# SmartSwitchBoard2x1.net
KiCad netlist of a schematic drawn in EAGLE
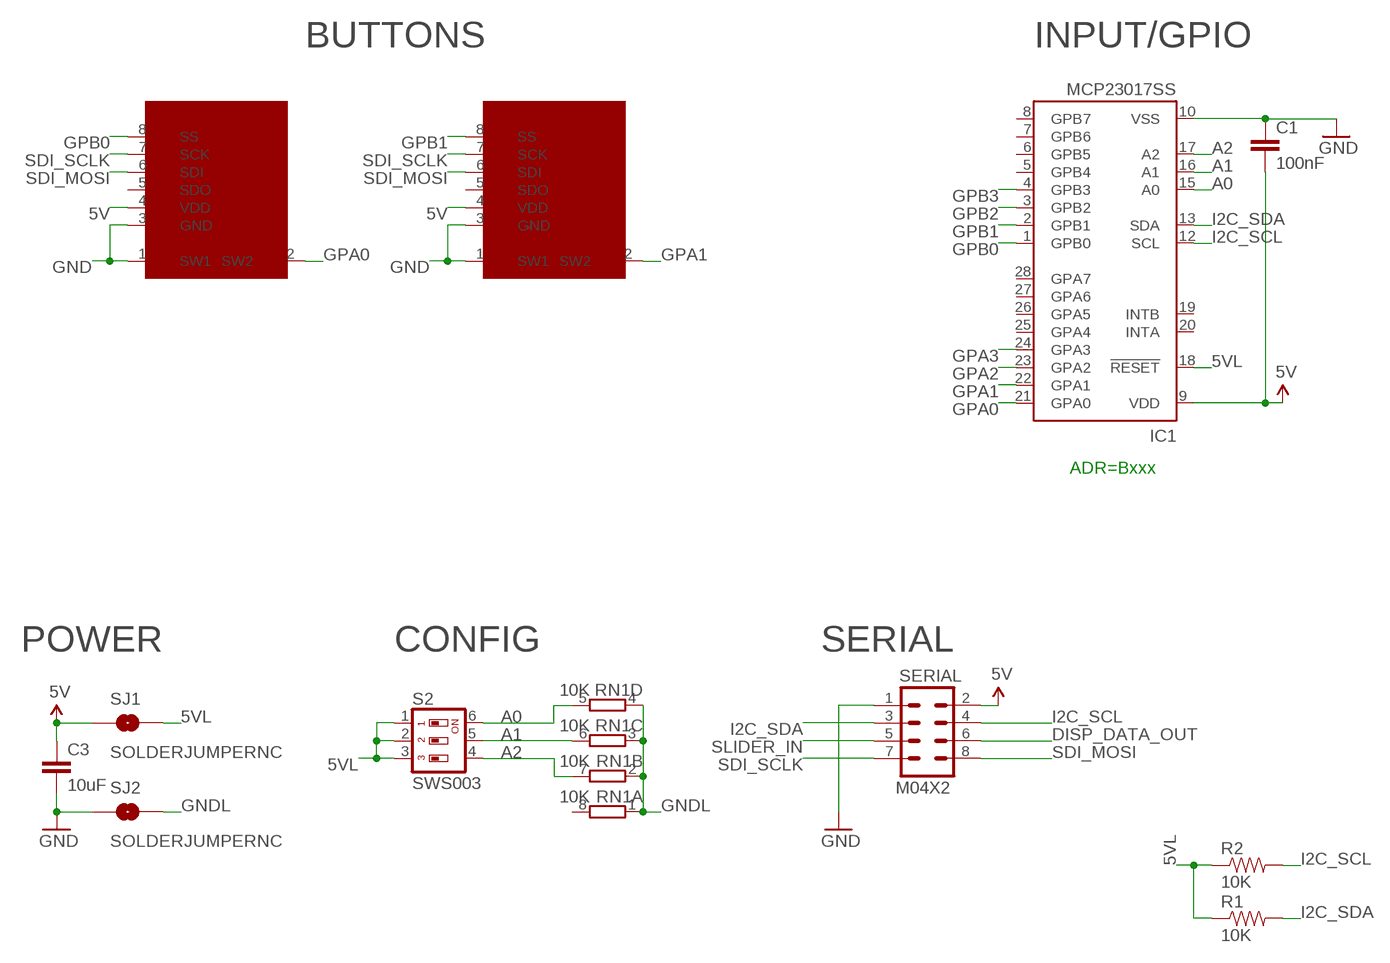
[diagram p0: schematic, sheet 1]

(export (version "E")
  (design (tool "Eeschema 10.0.6"))
  (components
    (comp (ref "C1")
      (value "100nF")
      (footprint "eagle-import:0603-CAP")
      (libsource (lib "eagle-import") (part "CAP0603-CAP"))
    )
    (comp (ref "C3")
      (value "10uF")
      (footprint "eagle-import:0805")
      (libsource (lib "eagle-import") (part "CAP0805"))
    )
    (comp (ref "IC1")
      (value "MCP23017SS")
      (footprint "eagle-import:SSOP28")
      (fields
        (field (name "MF") "MICROCHIP")
        (field (name "MPN") "MCP23017-E/SS")
        (field (name "MPN_1") "MCP23017-E/SS")
        (field (name "OC_FARNELL") "1467674")
        (field (name "OC_NEWARK") "31K2960")
      )
      (libsource (lib "eagle-import") (part "MCP23017SS"))
    )
    (comp (ref "R1")
      (value "10K")
      (footprint "eagle-import:0603-RES")
      (libsource (lib "eagle-import") (part "RESISTOR0603-RES"))
    )
    (comp (ref "R2")
      (value "10K")
      (footprint "eagle-import:0603-RES")
      (libsource (lib "eagle-import") (part "RESISTOR0603-RES"))
    )
    (comp (ref "RN1")
      (value "10K")
      (footprint "eagle-import:CAY16_HAND")
      (libsource (lib "eagle-import") (part "4R-NCAY16"))
    )
    (comp (ref "S2")
      (value "SWS003")
      (footprint "eagle-import:SMS-003")
      (libsource (lib "eagle-import") (part "SWS003"))
    )
    (comp (ref "SERIAL")
      (value "M04X2")
      (footprint "eagle-import:2X4")
      (libsource (lib "eagle-import") (part "M04X2"))
    )
    (comp (ref "SJ1")
      (value "SOLDERJUMPERNC")
      (footprint "eagle-import:SJ_2S")
      (libsource (lib "eagle-import") (part "SOLDERJUMPERNC"))
    )
    (comp (ref "SJ2")
      (value "SOLDERJUMPERNC")
      (footprint "eagle-import:SJ_2S")
      (libsource (lib "eagle-import") (part "SOLDERJUMPERNC"))
    )
    (comp (ref "U$2")
      (value "SMART_SWITCHSMART_SWITCH_8PIN")
      (footprint "eagle-import:SMART_SWITCH")
      (libsource (lib "eagle-import") (part "SMART_SWITCHSMART_SWITCH_8PIN"))
    )
    (comp (ref "U$3")
      (value "SMART_SWITCHSMART_SWITCH_8PIN")
      (footprint "eagle-import:SMART_SWITCH")
      (libsource (lib "eagle-import") (part "SMART_SWITCHSMART_SWITCH_8PIN"))
    )
  )
  (nets
    (net (code "1") (name "/5VL") (class "Default")
      (node (ref "IC1") (pin "18") (pinfunction "~{RESET}_18") (pintype "input"))
      (node (ref "R1") (pin "1") (pinfunction "1_1") (pintype "passive"))
      (node (ref "R2") (pin "1") (pinfunction "1_1") (pintype "passive"))
      (node (ref "S2") (pin "1") (pinfunction "1_1") (pintype "passive"))
      (node (ref "S2") (pin "2") (pinfunction "2_2") (pintype "passive"))
      (node (ref "S2") (pin "3") (pinfunction "3_3") (pintype "passive"))
      (node (ref "SJ1") (pin "2") (pinfunction "2_2") (pintype "passive"))
    )
    (net (code "2") (name "/A0") (class "Default")
      (node (ref "IC1") (pin "15") (pinfunction "A0_15") (pintype "input"))
      (node (ref "RN1") (pin "5") (pinfunction "2_5") (pintype "passive"))
      (node (ref "S2") (pin "6") (pinfunction "6_6") (pintype "passive"))
    )
    (net (code "3") (name "/A1") (class "Default")
      (node (ref "IC1") (pin "16") (pinfunction "A1_16") (pintype "input"))
      (node (ref "RN1") (pin "6") (pinfunction "2_6") (pintype "passive"))
      (node (ref "S2") (pin "5") (pinfunction "5_5") (pintype "passive"))
    )
    (net (code "4") (name "/A2") (class "Default")
      (node (ref "IC1") (pin "17") (pinfunction "A2_17") (pintype "input"))
      (node (ref "RN1") (pin "7") (pinfunction "2_7") (pintype "passive"))
      (node (ref "S2") (pin "4") (pinfunction "4_4") (pintype "passive"))
    )
    (net (code "5") (name "/DISP_DATA_OUT") (class "Default")
      (node (ref "SERIAL") (pin "6") (pinfunction "6_6") (pintype "passive"))
    )
    (net (code "6") (name "/GNDL") (class "Default")
      (node (ref "RN1") (pin "1") (pinfunction "1_1") (pintype "passive"))
      (node (ref "RN1") (pin "2") (pinfunction "1_2") (pintype "passive"))
      (node (ref "RN1") (pin "3") (pinfunction "1_3") (pintype "passive"))
      (node (ref "RN1") (pin "4") (pinfunction "1_4") (pintype "passive"))
      (node (ref "SJ2") (pin "2") (pinfunction "2_2") (pintype "passive"))
    )
    (net (code "7") (name "/GPA0") (class "Default")
      (node (ref "IC1") (pin "21") (pinfunction "GPA0_21") (pintype "bidirectional"))
      (node (ref "U$2") (pin "2") (pinfunction "SW2_2") (pintype "bidirectional"))
    )
    (net (code "8") (name "/GPA1") (class "Default")
      (node (ref "IC1") (pin "22") (pinfunction "GPA1_22") (pintype "bidirectional"))
      (node (ref "U$3") (pin "2") (pinfunction "SW2_2") (pintype "bidirectional"))
    )
    (net (code "9") (name "/GPA2") (class "Default")
      (node (ref "IC1") (pin "23") (pinfunction "GPA2_23") (pintype "bidirectional"))
    )
    (net (code "10") (name "/GPA3") (class "Default")
      (node (ref "IC1") (pin "24") (pinfunction "GPA3_24") (pintype "bidirectional"))
    )
    (net (code "11") (name "/GPB0") (class "Default")
      (node (ref "IC1") (pin "1") (pinfunction "GPB0_1") (pintype "bidirectional"))
      (node (ref "U$2") (pin "8") (pinfunction "SS_8") (pintype "bidirectional"))
    )
    (net (code "12") (name "/GPB1") (class "Default")
      (node (ref "IC1") (pin "2") (pinfunction "GPB1_2") (pintype "bidirectional"))
      (node (ref "U$3") (pin "8") (pinfunction "SS_8") (pintype "bidirectional"))
    )
    (net (code "13") (name "/GPB2") (class "Default")
      (node (ref "IC1") (pin "3") (pinfunction "GPB2_3") (pintype "bidirectional"))
    )
    (net (code "14") (name "/GPB3") (class "Default")
      (node (ref "IC1") (pin "4") (pinfunction "GPB3_4") (pintype "bidirectional"))
    )
    (net (code "15") (name "/I2C_SCL") (class "Default")
      (node (ref "IC1") (pin "12") (pinfunction "SCL_12") (pintype "input"))
      (node (ref "R2") (pin "2") (pinfunction "2_2") (pintype "passive"))
      (node (ref "SERIAL") (pin "4") (pinfunction "4_4") (pintype "passive"))
    )
    (net (code "16") (name "/I2C_SDA") (class "Default")
      (node (ref "IC1") (pin "13") (pinfunction "SDA_13") (pintype "bidirectional"))
      (node (ref "R1") (pin "2") (pinfunction "2_2") (pintype "passive"))
      (node (ref "SERIAL") (pin "3") (pinfunction "3_3") (pintype "passive"))
    )
    (net (code "17") (name "/SDI_MOSI") (class "Default")
      (node (ref "SERIAL") (pin "8") (pinfunction "8_8") (pintype "passive"))
      (node (ref "U$2") (pin "6") (pinfunction "SDI_6") (pintype "bidirectional"))
      (node (ref "U$3") (pin "6") (pinfunction "SDI_6") (pintype "bidirectional"))
    )
    (net (code "18") (name "/SDI_SCLK") (class "Default")
      (node (ref "SERIAL") (pin "7") (pinfunction "7_7") (pintype "passive"))
      (node (ref "U$2") (pin "7") (pinfunction "SCK_7") (pintype "bidirectional"))
      (node (ref "U$3") (pin "7") (pinfunction "SCK_7") (pintype "bidirectional"))
    )
    (net (code "19") (name "/SLIDER_IN") (class "Default")
      (node (ref "SERIAL") (pin "5") (pinfunction "5_5") (pintype "passive"))
    )
    (net (code "20") (name "5V") (class "Default")
      (node (ref "C1") (pin "2") (pinfunction "2_2") (pintype "passive"))
      (node (ref "C3") (pin "1") (pinfunction "1_1") (pintype "passive"))
      (node (ref "IC1") (pin "9") (pinfunction "VDD_9") (pintype "power_in"))
      (node (ref "SERIAL") (pin "2") (pinfunction "2_2") (pintype "passive"))
      (node (ref "SJ1") (pin "1") (pinfunction "1_1") (pintype "passive"))
      (node (ref "U$2") (pin "4") (pinfunction "VDD_4") (pintype "bidirectional"))
      (node (ref "U$3") (pin "4") (pinfunction "VDD_4") (pintype "bidirectional"))
    )
    (net (code "21") (name "GND") (class "Default")
      (node (ref "C1") (pin "1") (pinfunction "1_1") (pintype "passive"))
      (node (ref "C3") (pin "2") (pinfunction "2_2") (pintype "passive"))
      (node (ref "IC1") (pin "10") (pinfunction "VSS_10") (pintype "power_in"))
      (node (ref "SERIAL") (pin "1") (pinfunction "1_1") (pintype "passive"))
      (node (ref "SJ2") (pin "1") (pinfunction "1_1") (pintype "passive"))
      (node (ref "U$2") (pin "1") (pinfunction "SW1_1") (pintype "bidirectional"))
      (node (ref "U$2") (pin "3") (pinfunction "GND_3") (pintype "bidirectional"))
      (node (ref "U$3") (pin "1") (pinfunction "SW1_1") (pintype "bidirectional"))
      (node (ref "U$3") (pin "3") (pinfunction "GND_3") (pintype "bidirectional"))
    )
    (net (code "22") (name "unconnected-(IC1-GPA4-Pad25)") (class "Default")
      (node (ref "IC1") (pin "25") (pinfunction "GPA4_25") (pintype "bidirectional"))
    )
    (net (code "23") (name "unconnected-(IC1-GPA5-Pad26)") (class "Default")
      (node (ref "IC1") (pin "26") (pinfunction "GPA5_26") (pintype "bidirectional"))
    )
    (net (code "24") (name "unconnected-(IC1-GPA6-Pad27)") (class "Default")
      (node (ref "IC1") (pin "27") (pinfunction "GPA6_27") (pintype "bidirectional"))
    )
    (net (code "25") (name "unconnected-(IC1-GPA7-Pad28)") (class "Default")
      (node (ref "IC1") (pin "28") (pinfunction "GPA7_28") (pintype "bidirectional"))
    )
    (net (code "26") (name "unconnected-(IC1-GPB4-Pad5)") (class "Default")
      (node (ref "IC1") (pin "5") (pinfunction "GPB4_5") (pintype "bidirectional"))
    )
    (net (code "27") (name "unconnected-(IC1-GPB5-Pad6)") (class "Default")
      (node (ref "IC1") (pin "6") (pinfunction "GPB5_6") (pintype "bidirectional"))
    )
    (net (code "28") (name "unconnected-(IC1-GPB6-Pad7)") (class "Default")
      (node (ref "IC1") (pin "7") (pinfunction "GPB6_7") (pintype "bidirectional"))
    )
    (net (code "29") (name "unconnected-(IC1-GPB7-Pad8)") (class "Default")
      (node (ref "IC1") (pin "8") (pinfunction "GPB7_8") (pintype "bidirectional"))
    )
    (net (code "30") (name "unconnected-(IC1-INTA-Pad20)") (class "Default")
      (node (ref "IC1") (pin "20") (pinfunction "INTA_20") (pintype "output"))
    )
    (net (code "31") (name "unconnected-(IC1-INTB-Pad19)") (class "Default")
      (node (ref "IC1") (pin "19") (pinfunction "INTB_19") (pintype "output"))
    )
    (net (code "32") (name "unconnected-(RN1A-2-Pad8)") (class "Default")
      (node (ref "RN1") (pin "8") (pinfunction "2_8") (pintype "passive"))
    )
    (net (code "33") (name "unconnected-(U$2-SDO-Pad5)") (class "Default")
      (node (ref "U$2") (pin "5") (pinfunction "SDO_5") (pintype "bidirectional"))
    )
    (net (code "34") (name "unconnected-(U$3-SDO-Pad5)") (class "Default")
      (node (ref "U$3") (pin "5") (pinfunction "SDO_5") (pintype "bidirectional"))
    )
  )
)
